# TeslaBMS_Shield_5.net
KiCad netlist of a schematic drawn in EAGLE
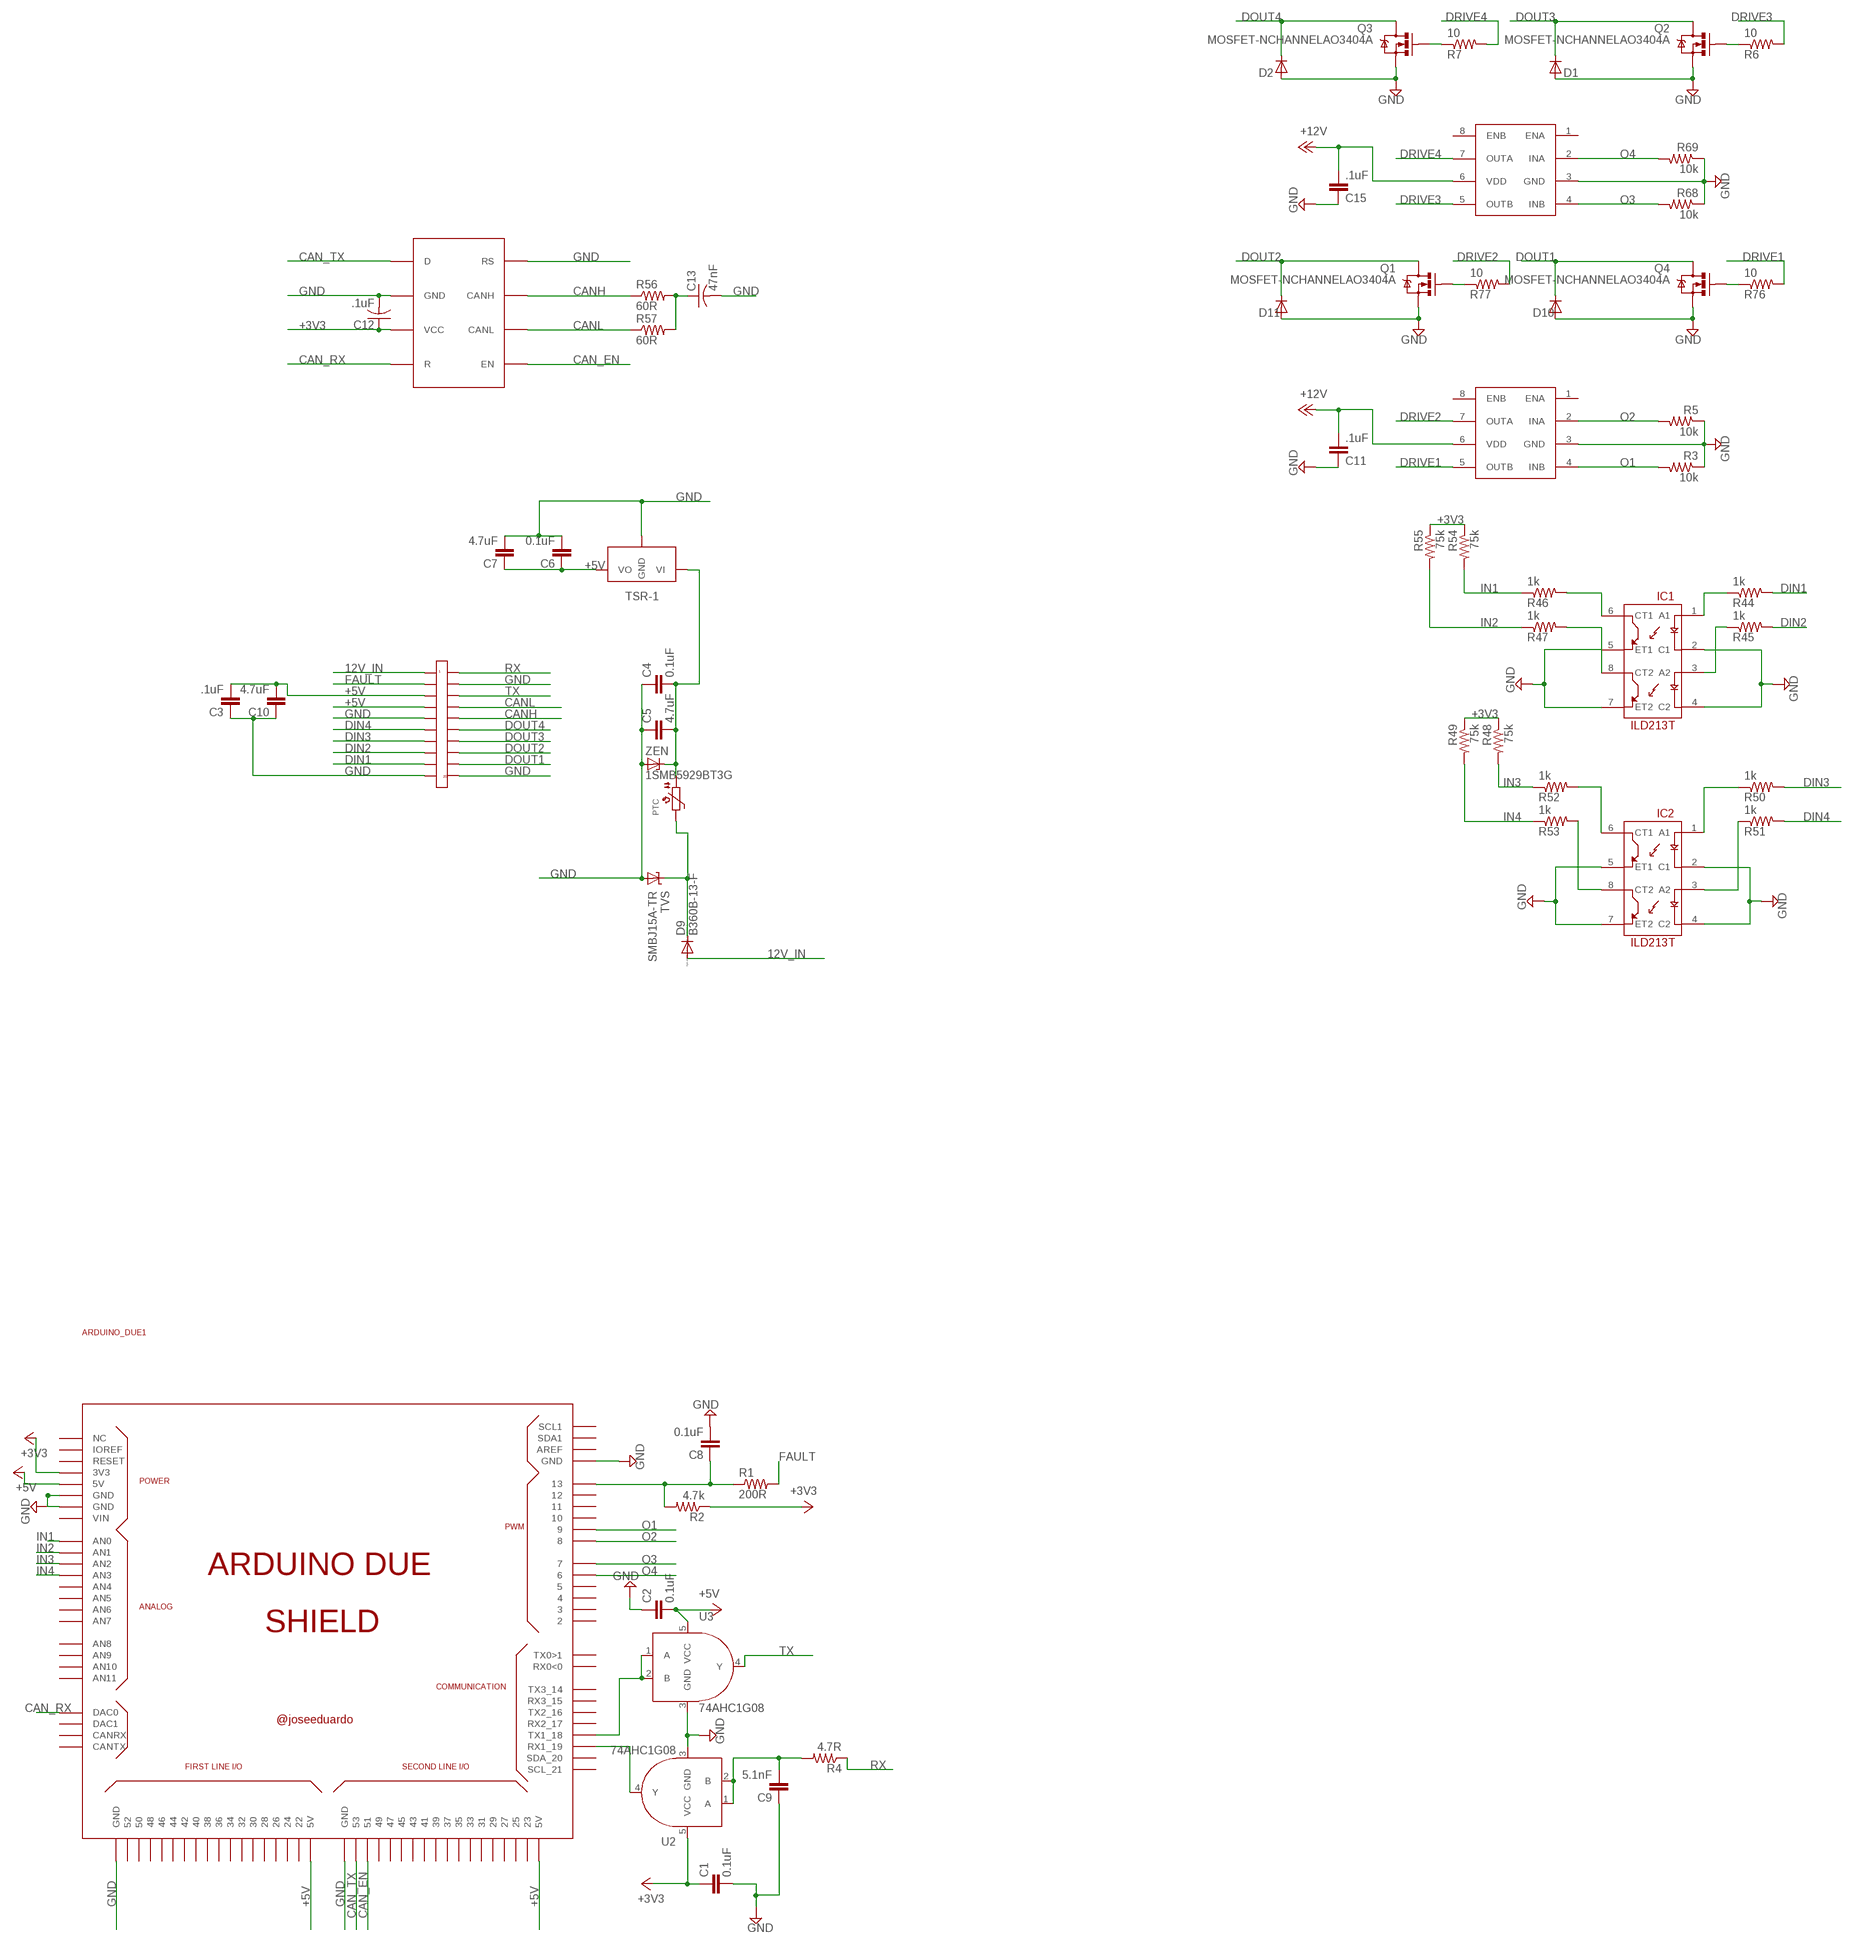
[diagram p0: schematic, sheet 1]

(export (version "E")
  (design (tool "Eeschema 10.0.6"))
  (components
    (comp (ref "ARDUINO_DUE1")
      (value "ARDUINO_DUE_SHIELD")
      (footprint "eagle-import:ARDUINO_DUE_SHIELD")
      (libsource (lib "eagle-import") (part "ARDUINO_DUE_SHIELD"))
    )
    (comp (ref "C1")
      (value "0.1uF")
      (footprint "eagle-import:0603-CAP")
      (libsource (lib "eagle-import") (part "CAP0603-CAP"))
    )
    (comp (ref "C2")
      (value "0.1uF")
      (footprint "eagle-import:0603-CAP")
      (libsource (lib "eagle-import") (part "CAP0603-CAP"))
    )
    (comp (ref "C3")
      (value ".1uF")
      (footprint "eagle-import:0603-CAP")
      (libsource (lib "eagle-import") (part "CAP0603-CAP"))
    )
    (comp (ref "C4")
      (value "0.1uF")
      (footprint "eagle-import:0805")
      (libsource (lib "eagle-import") (part "CAP0805"))
    )
    (comp (ref "C5")
      (value "4.7uF")
      (footprint "eagle-import:0805")
      (libsource (lib "eagle-import") (part "CAP0805"))
    )
    (comp (ref "C6")
      (value "0.1uF")
      (footprint "eagle-import:0805")
      (libsource (lib "eagle-import") (part "CAP0805"))
    )
    (comp (ref "C7")
      (value "4.7uF")
      (footprint "eagle-import:0805")
      (libsource (lib "eagle-import") (part "CAP0805"))
    )
    (comp (ref "C8")
      (value "0.1uF")
      (footprint "eagle-import:0603-CAP")
      (libsource (lib "eagle-import") (part "CAP0603-CAP"))
    )
    (comp (ref "C9")
      (value "5.1nF")
      (footprint "eagle-import:0603-CAP")
      (libsource (lib "eagle-import") (part "CAP0603-CAP"))
    )
    (comp (ref "C10")
      (value "4.7uF")
      (footprint "eagle-import:0603-CAP")
      (libsource (lib "eagle-import") (part "CAP0603-CAP"))
    )
    (comp (ref "C11")
      (value ".1uF")
      (footprint "eagle-import:0603-CAP")
      (libsource (lib "eagle-import") (part "CAP0603-CAP"))
    )
    (comp (ref "C12")
      (value ".1uF")
      (footprint "eagle-import:C0603")
      (libsource (lib "eagle-import") (part "C-USC0603"))
    )
    (comp (ref "C13")
      (value "47nF")
      (footprint "eagle-import:C0805")
      (libsource (lib "eagle-import") (part "C-USC0805"))
    )
    (comp (ref "C15")
      (value ".1uF")
      (footprint "eagle-import:0603-CAP")
      (libsource (lib "eagle-import") (part "CAP0603-CAP"))
    )
    (comp (ref "D1")
      (value "MBR0520LT")
      (footprint "eagle-import:SOD123")
      (libsource (lib "eagle-import") (part "MBR0520LT"))
    )
    (comp (ref "D2")
      (value "MBR0520LT")
      (footprint "eagle-import:SOD123")
      (libsource (lib "eagle-import") (part "MBR0520LT"))
    )
    (comp (ref "D9")
      (value "B360B-13-F")
      (footprint "eagle-import:SMB")
      (libsource (lib "eagle-import") (part "DIODE-SMB"))
    )
    (comp (ref "D10")
      (value "MBR0520LT")
      (footprint "eagle-import:SOD123")
      (libsource (lib "eagle-import") (part "MBR0520LT"))
    )
    (comp (ref "D11")
      (value "MBR0520LT")
      (footprint "eagle-import:SOD123")
      (libsource (lib "eagle-import") (part "MBR0520LT"))
    )
    (comp (ref "IC1")
      (value "ILD213T")
      (footprint "eagle-import:SO08")
      (libsource (lib "eagle-import") (part "ILD213T"))
    )
    (comp (ref "IC2")
      (value "ILD213T")
      (footprint "eagle-import:SO08")
      (libsource (lib "eagle-import") (part "ILD213T"))
    )
    (comp (ref "PTC")
      (value "PTC1812")
      (footprint "eagle-import:PTC1812")
      (libsource (lib "eagle-import") (part "PTC1812"))
    )
    (comp (ref "Q1")
      (value "MOSFET-NCHANNELAO3404A")
      (footprint "eagle-import:SOT23-3")
      (libsource (lib "eagle-import") (part "MOSFET-NCHANNELAO3404A"))
    )
    (comp (ref "Q2")
      (value "MOSFET-NCHANNELAO3404A")
      (footprint "eagle-import:SOT23-3")
      (libsource (lib "eagle-import") (part "MOSFET-NCHANNELAO3404A"))
    )
    (comp (ref "Q3")
      (value "MOSFET-NCHANNELAO3404A")
      (footprint "eagle-import:SOT23-3")
      (libsource (lib "eagle-import") (part "MOSFET-NCHANNELAO3404A"))
    )
    (comp (ref "Q4")
      (value "MOSFET-NCHANNELAO3404A")
      (footprint "eagle-import:SOT23-3")
      (libsource (lib "eagle-import") (part "MOSFET-NCHANNELAO3404A"))
    )
    (comp (ref "R1")
      (value "200R")
      (footprint "eagle-import:0603-RES")
      (libsource (lib "eagle-import") (part "RESISTOR0603-RES"))
    )
    (comp (ref "R2")
      (value "4.7k")
      (footprint "eagle-import:0603-RES")
      (libsource (lib "eagle-import") (part "RESISTOR0603-RES"))
    )
    (comp (ref "R3")
      (value "10k")
      (footprint "eagle-import:R0402")
      (libsource (lib "eagle-import") (part "R-US_R0402"))
    )
    (comp (ref "R4")
      (value "4.7R")
      (footprint "eagle-import:0603-RES")
      (libsource (lib "eagle-import") (part "RESISTOR0603-RES"))
    )
    (comp (ref "R5")
      (value "10k")
      (footprint "eagle-import:R0402")
      (libsource (lib "eagle-import") (part "R-US_R0402"))
    )
    (comp (ref "R6")
      (value "10")
      (footprint "eagle-import:R0402")
      (libsource (lib "eagle-import") (part "R-US_R0402"))
    )
    (comp (ref "R7")
      (value "10")
      (footprint "eagle-import:R0402")
      (libsource (lib "eagle-import") (part "R-US_R0402"))
    )
    (comp (ref "R44")
      (value "1k")
      (footprint "eagle-import:0603-RES")
      (libsource (lib "eagle-import") (part "RESISTOR0603-RES"))
    )
    (comp (ref "R45")
      (value "1k")
      (footprint "eagle-import:0603-RES")
      (libsource (lib "eagle-import") (part "RESISTOR0603-RES"))
    )
    (comp (ref "R46")
      (value "1k")
      (footprint "eagle-import:0603-RES")
      (libsource (lib "eagle-import") (part "RESISTOR0603-RES"))
    )
    (comp (ref "R47")
      (value "1k")
      (footprint "eagle-import:0603-RES")
      (libsource (lib "eagle-import") (part "RESISTOR0603-RES"))
    )
    (comp (ref "R48")
      (value "75k")
      (footprint "eagle-import:0603-RES")
      (libsource (lib "eagle-import") (part "RESISTOR0603-RES"))
    )
    (comp (ref "R49")
      (value "75k")
      (footprint "eagle-import:0603-RES")
      (libsource (lib "eagle-import") (part "RESISTOR0603-RES"))
    )
    (comp (ref "R50")
      (value "1k")
      (footprint "eagle-import:0603-RES")
      (libsource (lib "eagle-import") (part "RESISTOR0603-RES"))
    )
    (comp (ref "R51")
      (value "1k")
      (footprint "eagle-import:0603-RES")
      (libsource (lib "eagle-import") (part "RESISTOR0603-RES"))
    )
    (comp (ref "R52")
      (value "1k")
      (footprint "eagle-import:0603-RES")
      (libsource (lib "eagle-import") (part "RESISTOR0603-RES"))
    )
    (comp (ref "R53")
      (value "1k")
      (footprint "eagle-import:0603-RES")
      (libsource (lib "eagle-import") (part "RESISTOR0603-RES"))
    )
    (comp (ref "R54")
      (value "75k")
      (footprint "eagle-import:0603-RES")
      (libsource (lib "eagle-import") (part "RESISTOR0603-RES"))
    )
    (comp (ref "R55")
      (value "75k")
      (footprint "eagle-import:0603-RES")
      (libsource (lib "eagle-import") (part "RESISTOR0603-RES"))
    )
    (comp (ref "R56")
      (value "60R")
      (footprint "eagle-import:M0805")
      (libsource (lib "eagle-import") (part "R-US_M0805"))
    )
    (comp (ref "R57")
      (value "60R")
      (footprint "eagle-import:M0805")
      (libsource (lib "eagle-import") (part "R-US_M0805"))
    )
    (comp (ref "R68")
      (value "10k")
      (footprint "eagle-import:R0402")
      (libsource (lib "eagle-import") (part "R-US_R0402"))
    )
    (comp (ref "R69")
      (value "10k")
      (footprint "eagle-import:R0402")
      (libsource (lib "eagle-import") (part "R-US_R0402"))
    )
    (comp (ref "R76")
      (value "10")
      (footprint "eagle-import:R0402")
      (libsource (lib "eagle-import") (part "R-US_R0402"))
    )
    (comp (ref "R77")
      (value "10")
      (footprint "eagle-import:R0402")
      (libsource (lib "eagle-import") (part "R-US_R0402"))
    )
    (comp (ref "TVS")
      (value "SMBJ15A-TR")
      (footprint "eagle-import:SMBJ")
      (libsource (lib "eagle-import") (part "SUPPRESSOR-SMBJ"))
    )
    (comp (ref "U$2")
      (value "VAL-U-LOK-20PIN")
      (footprint "eagle-import:VALULOK-20")
      (libsource (lib "eagle-import") (part "VAL-U-LOK-20PIN"))
    )
    (comp (ref "U1")
      (value "SN65HVD234")
      (footprint "eagle-import:SOIC8")
      (libsource (lib "eagle-import") (part "SN65HVD234"))
    )
    (comp (ref "U2")
      (value "74AHC1G08")
      (footprint "eagle-import:SOT353")
      (libsource (lib "eagle-import") (part "74AHC1G08"))
    )
    (comp (ref "U3")
      (value "74AHC1G08")
      (footprint "eagle-import:SOT353")
      (libsource (lib "eagle-import") (part "74AHC1G08"))
    )
    (comp (ref "U4")
      (value "FAN3227")
      (footprint "eagle-import:SOIC8")
      (libsource (lib "eagle-import") (part "FAN3227"))
    )
    (comp (ref "U5")
      (value "FAN3227")
      (footprint "eagle-import:SOIC8")
      (libsource (lib "eagle-import") (part "FAN3227"))
    )
    (comp (ref "U9")
      (value "TSR-1")
      (footprint "eagle-import:TSR-1")
      (libsource (lib "eagle-import") (part "TSR-1"))
    )
    (comp (ref "ZEN")
      (value "1SMB5929BT3G")
      (footprint "eagle-import:SMB")
      (libsource (lib "eagle-import") (part "ZENER-DIODESMB"))
    )
  )
  (nets
    (net (code "1") (name "+3V3") (class "Default")
      (node (ref "ARDUINO_DUE1") (pin "3V3") (pinfunction "3V3_3V3") (pintype "bidirectional"))
      (node (ref "C1") (pin "1") (pinfunction "1_1") (pintype "passive"))
      (node (ref "C12") (pin "1") (pinfunction "1_1") (pintype "passive"))
      (node (ref "R2") (pin "1") (pinfunction "1_1") (pintype "passive"))
      (node (ref "R48") (pin "1") (pinfunction "1_1") (pintype "passive"))
      (node (ref "R49") (pin "1") (pinfunction "1_1") (pintype "passive"))
      (node (ref "R54") (pin "1") (pinfunction "1_1") (pintype "passive"))
      (node (ref "R55") (pin "1") (pinfunction "1_1") (pintype "passive"))
      (node (ref "U1") (pin "PIN3") (pinfunction "VCC_PIN3") (pintype "bidirectional"))
      (node (ref "U2") (pin "5") (pinfunction "VCC_5") (pintype "bidirectional"))
    )
    (net (code "2") (name "+5V") (class "Default")
      (node (ref "ARDUINO_DUE1") (pin "5V0") (pinfunction "5V_5V0") (pintype "bidirectional"))
      (node (ref "ARDUINO_DUE1") (pin "5V0_1") (pinfunction "5V_5V0_1") (pintype "bidirectional"))
      (node (ref "ARDUINO_DUE1") (pin "5V0_2") (pinfunction "5V_5V0_2") (pintype "bidirectional"))
      (node (ref "C10") (pin "2") (pinfunction "2_2") (pintype "passive"))
      (node (ref "C2") (pin "2") (pinfunction "2_2") (pintype "passive"))
      (node (ref "C3") (pin "2") (pinfunction "2_2") (pintype "passive"))
      (node (ref "C6") (pin "1") (pinfunction "1_1") (pintype "passive"))
      (node (ref "C7") (pin "1") (pinfunction "1_1") (pintype "passive"))
      (node (ref "U$2") (pin "P$3") (pinfunction "P$3_P$3") (pintype "bidirectional"))
      (node (ref "U$2") (pin "P$4") (pinfunction "P$4_P$4") (pintype "bidirectional"))
      (node (ref "U3") (pin "5") (pinfunction "VCC_5") (pintype "bidirectional"))
      (node (ref "U9") (pin "P$3") (pinfunction "VO_P$3") (pintype "bidirectional"))
    )
    (net (code "3") (name "+12V") (class "Default")
      (node (ref "C11") (pin "2") (pinfunction "2_2") (pintype "passive"))
      (node (ref "C15") (pin "2") (pinfunction "2_2") (pintype "passive"))
      (node (ref "C4") (pin "2") (pinfunction "2_2") (pintype "passive"))
      (node (ref "C5") (pin "2") (pinfunction "2_2") (pintype "passive"))
      (node (ref "PTC") (pin "P$1") (pinfunction "1_P$1") (pintype "passive"))
      (node (ref "U4") (pin "6") (pinfunction "VDD_6") (pintype "bidirectional"))
      (node (ref "U5") (pin "6") (pinfunction "VDD_6") (pintype "bidirectional"))
      (node (ref "U9") (pin "P$1") (pinfunction "VI_P$1") (pintype "bidirectional"))
      (node (ref "ZEN") (pin "C") (pinfunction "C_C") (pintype "passive"))
    )
    (net (code "4") (name "/12V_IN") (class "Default")
      (node (ref "D9") (pin "A") (pinfunction "A_A") (pintype "passive"))
      (node (ref "U$2") (pin "P$1") (pinfunction "P$1_P$1") (pintype "bidirectional"))
    )
    (net (code "5") (name "/CANH") (class "Default")
      (node (ref "R56") (pin "1") (pinfunction "1_1") (pintype "passive"))
      (node (ref "U$2") (pin "P$15") (pinfunction "P$15_P$15") (pintype "bidirectional"))
      (node (ref "U1") (pin "PIN7") (pinfunction "CANH_PIN7") (pintype "bidirectional"))
    )
    (net (code "6") (name "/CANL") (class "Default")
      (node (ref "R57") (pin "1") (pinfunction "1_1") (pintype "passive"))
      (node (ref "U$2") (pin "P$14") (pinfunction "P$14_P$14") (pintype "bidirectional"))
      (node (ref "U1") (pin "PIN6") (pinfunction "CANL_PIN6") (pintype "bidirectional"))
    )
    (net (code "7") (name "/CAN_EN") (class "Default")
      (node (ref "ARDUINO_DUE1") (pin "51") (pinfunction "51_51") (pintype "bidirectional"))
      (node (ref "U1") (pin "PIN5") (pinfunction "EN_PIN5") (pintype "bidirectional"))
    )
    (net (code "8") (name "/CAN_RX") (class "Default")
      (node (ref "ARDUINO_DUE1") (pin "DAC0") (pinfunction "DAC0_DAC0") (pintype "bidirectional"))
      (node (ref "U1") (pin "PIN4") (pinfunction "R_PIN4") (pintype "bidirectional"))
    )
    (net (code "9") (name "/CAN_TX") (class "Default")
      (node (ref "ARDUINO_DUE1") (pin "53") (pinfunction "53_53") (pintype "bidirectional"))
      (node (ref "U1") (pin "PIN1") (pinfunction "D_PIN1") (pintype "bidirectional"))
    )
    (net (code "10") (name "/DIN1") (class "Default")
      (node (ref "R44") (pin "2") (pinfunction "2_2") (pintype "passive"))
      (node (ref "U$2") (pin "P$9") (pinfunction "P$9_P$9") (pintype "bidirectional"))
    )
    (net (code "11") (name "/DIN2") (class "Default")
      (node (ref "R45") (pin "2") (pinfunction "2_2") (pintype "passive"))
      (node (ref "U$2") (pin "P$8") (pinfunction "P$8_P$8") (pintype "bidirectional"))
    )
    (net (code "12") (name "/DIN3") (class "Default")
      (node (ref "R50") (pin "2") (pinfunction "2_2") (pintype "passive"))
      (node (ref "U$2") (pin "P$7") (pinfunction "P$7_P$7") (pintype "bidirectional"))
    )
    (net (code "13") (name "/DIN4") (class "Default")
      (node (ref "R51") (pin "2") (pinfunction "2_2") (pintype "passive"))
      (node (ref "U$2") (pin "P$6") (pinfunction "P$6_P$6") (pintype "bidirectional"))
    )
    (net (code "14") (name "/DOUT1") (class "Default")
      (node (ref "D10") (pin "C") (pinfunction "C_C") (pintype "passive"))
      (node (ref "Q4") (pin "3") (pinfunction "D_3") (pintype "passive"))
      (node (ref "U$2") (pin "P$19") (pinfunction "P$19_P$19") (pintype "bidirectional"))
    )
    (net (code "15") (name "/DOUT2") (class "Default")
      (node (ref "D11") (pin "C") (pinfunction "C_C") (pintype "passive"))
      (node (ref "Q1") (pin "3") (pinfunction "D_3") (pintype "passive"))
      (node (ref "U$2") (pin "P$18") (pinfunction "P$18_P$18") (pintype "bidirectional"))
    )
    (net (code "16") (name "/DOUT3") (class "Default")
      (node (ref "D1") (pin "C") (pinfunction "C_C") (pintype "passive"))
      (node (ref "Q2") (pin "3") (pinfunction "D_3") (pintype "passive"))
      (node (ref "U$2") (pin "P$17") (pinfunction "P$17_P$17") (pintype "bidirectional"))
    )
    (net (code "17") (name "/DOUT4") (class "Default")
      (node (ref "D2") (pin "C") (pinfunction "C_C") (pintype "passive"))
      (node (ref "Q3") (pin "3") (pinfunction "D_3") (pintype "passive"))
      (node (ref "U$2") (pin "P$16") (pinfunction "P$16_P$16") (pintype "bidirectional"))
    )
    (net (code "18") (name "/DRIVE1") (class "Default")
      (node (ref "R76") (pin "2") (pinfunction "2_2") (pintype "passive"))
      (node (ref "U5") (pin "5") (pinfunction "OUTB_5") (pintype "bidirectional"))
    )
    (net (code "19") (name "/DRIVE2") (class "Default")
      (node (ref "R77") (pin "2") (pinfunction "2_2") (pintype "passive"))
      (node (ref "U5") (pin "7") (pinfunction "OUTA_7") (pintype "bidirectional"))
    )
    (net (code "20") (name "/DRIVE3") (class "Default")
      (node (ref "R6") (pin "2") (pinfunction "2_2") (pintype "passive"))
      (node (ref "U4") (pin "5") (pinfunction "OUTB_5") (pintype "bidirectional"))
    )
    (net (code "21") (name "/DRIVE4") (class "Default")
      (node (ref "R7") (pin "2") (pinfunction "2_2") (pintype "passive"))
      (node (ref "U4") (pin "7") (pinfunction "OUTA_7") (pintype "bidirectional"))
    )
    (net (code "22") (name "/FAULT") (class "Default")
      (node (ref "R1") (pin "2") (pinfunction "2_2") (pintype "passive"))
      (node (ref "U$2") (pin "P$2") (pinfunction "P$2_P$2") (pintype "bidirectional"))
    )
    (net (code "23") (name "/IN1") (class "Default")
      (node (ref "ARDUINO_DUE1") (pin "A0") (pinfunction "AN0_A0") (pintype "bidirectional"))
      (node (ref "R46") (pin "1") (pinfunction "1_1") (pintype "passive"))
      (node (ref "R54") (pin "2") (pinfunction "2_2") (pintype "passive"))
    )
    (net (code "24") (name "/IN2") (class "Default")
      (node (ref "ARDUINO_DUE1") (pin "A1") (pinfunction "AN1_A1") (pintype "bidirectional"))
      (node (ref "R47") (pin "1") (pinfunction "1_1") (pintype "passive"))
      (node (ref "R55") (pin "2") (pinfunction "2_2") (pintype "passive"))
    )
    (net (code "25") (name "/IN3") (class "Default")
      (node (ref "ARDUINO_DUE1") (pin "A2") (pinfunction "AN2_A2") (pintype "bidirectional"))
      (node (ref "R48") (pin "2") (pinfunction "2_2") (pintype "passive"))
      (node (ref "R52") (pin "1") (pinfunction "1_1") (pintype "passive"))
    )
    (net (code "26") (name "/IN4") (class "Default")
      (node (ref "ARDUINO_DUE1") (pin "A3") (pinfunction "AN3_A3") (pintype "bidirectional"))
      (node (ref "R49") (pin "2") (pinfunction "2_2") (pintype "passive"))
      (node (ref "R53") (pin "1") (pinfunction "1_1") (pintype "passive"))
    )
    (net (code "27") (name "/O1") (class "Default")
      (node (ref "ARDUINO_DUE1") (pin "9") (pinfunction "9_9") (pintype "bidirectional"))
      (node (ref "R3") (pin "2") (pinfunction "2_2") (pintype "passive"))
      (node (ref "U5") (pin "4") (pinfunction "INB_4") (pintype "bidirectional"))
    )
    (net (code "28") (name "/O2") (class "Default")
      (node (ref "ARDUINO_DUE1") (pin "8") (pinfunction "8_8") (pintype "bidirectional"))
      (node (ref "R5") (pin "2") (pinfunction "2_2") (pintype "passive"))
      (node (ref "U5") (pin "2") (pinfunction "INA_2") (pintype "bidirectional"))
    )
    (net (code "29") (name "/O3") (class "Default")
      (node (ref "ARDUINO_DUE1") (pin "7") (pinfunction "7_7") (pintype "bidirectional"))
      (node (ref "R68") (pin "2") (pinfunction "2_2") (pintype "passive"))
      (node (ref "U4") (pin "4") (pinfunction "INB_4") (pintype "bidirectional"))
    )
    (net (code "30") (name "/O4") (class "Default")
      (node (ref "ARDUINO_DUE1") (pin "6") (pinfunction "6_6") (pintype "bidirectional"))
      (node (ref "R69") (pin "2") (pinfunction "2_2") (pintype "passive"))
      (node (ref "U4") (pin "2") (pinfunction "INA_2") (pintype "bidirectional"))
    )
    (net (code "31") (name "/RX") (class "Default")
      (node (ref "R4") (pin "1") (pinfunction "1_1") (pintype "passive"))
      (node (ref "U$2") (pin "P$11") (pinfunction "P$11_P$11") (pintype "bidirectional"))
    )
    (net (code "32") (name "/TX") (class "Default")
      (node (ref "U$2") (pin "P$13") (pinfunction "P$13_P$13") (pintype "bidirectional"))
      (node (ref "U3") (pin "4") (pinfunction "Y_4") (pintype "bidirectional"))
    )
    (net (code "33") (name "GND") (class "Default")
      (node (ref "ARDUINO_DUE1") (pin "GND") (pinfunction "GND_GND") (pintype "bidirectional"))
      (node (ref "ARDUINO_DUE1") (pin "GND_1") (pinfunction "GND_GND_1") (pintype "bidirectional"))
      (node (ref "ARDUINO_DUE1") (pin "GND_2") (pinfunction "GND_GND_2") (pintype "bidirectional"))
      (node (ref "ARDUINO_DUE1") (pin "GND_3") (pinfunction "GND_GND_3") (pintype "bidirectional"))
      (node (ref "ARDUINO_DUE1") (pin "GND_4") (pinfunction "GND_GND_4") (pintype "bidirectional"))
      (node (ref "C1") (pin "2") (pinfunction "2_2") (pintype "passive"))
      (node (ref "C10") (pin "1") (pinfunction "1_1") (pintype "passive"))
      (node (ref "C11") (pin "1") (pinfunction "1_1") (pintype "passive"))
      (node (ref "C12") (pin "2") (pinfunction "2_2") (pintype "passive"))
      (node (ref "C13") (pin "2") (pinfunction "2_2") (pintype "passive"))
      (node (ref "C15") (pin "1") (pinfunction "1_1") (pintype "passive"))
      (node (ref "C2") (pin "1") (pinfunction "1_1") (pintype "passive"))
      (node (ref "C3") (pin "1") (pinfunction "1_1") (pintype "passive"))
      (node (ref "C4") (pin "1") (pinfunction "1_1") (pintype "passive"))
      (node (ref "C5") (pin "1") (pinfunction "1_1") (pintype "passive"))
      (node (ref "C6") (pin "2") (pinfunction "2_2") (pintype "passive"))
      (node (ref "C7") (pin "2") (pinfunction "2_2") (pintype "passive"))
      (node (ref "C8") (pin "2") (pinfunction "2_2") (pintype "passive"))
      (node (ref "C9") (pin "1") (pinfunction "1_1") (pintype "passive"))
      (node (ref "D1") (pin "A") (pinfunction "A_A") (pintype "passive"))
      (node (ref "D10") (pin "A") (pinfunction "A_A") (pintype "passive"))
      (node (ref "D11") (pin "A") (pinfunction "A_A") (pintype "passive"))
      (node (ref "D2") (pin "A") (pinfunction "A_A") (pintype "passive"))
      (node (ref "IC1") (pin "2") (pinfunction "C1_2") (pintype "bidirectional"))
      (node (ref "IC1") (pin "4") (pinfunction "C2_4") (pintype "bidirectional"))
      (node (ref "IC1") (pin "5") (pinfunction "ET1_5") (pintype "bidirectional"))
      (node (ref "IC1") (pin "7") (pinfunction "ET2_7") (pintype "bidirectional"))
      (node (ref "IC2") (pin "2") (pinfunction "C1_2") (pintype "bidirectional"))
      (node (ref "IC2") (pin "4") (pinfunction "C2_4") (pintype "bidirectional"))
      (node (ref "IC2") (pin "5") (pinfunction "ET1_5") (pintype "bidirectional"))
      (node (ref "IC2") (pin "7") (pinfunction "ET2_7") (pintype "bidirectional"))
      (node (ref "Q1") (pin "2") (pinfunction "S_2") (pintype "passive"))
      (node (ref "Q2") (pin "2") (pinfunction "S_2") (pintype "passive"))
      (node (ref "Q3") (pin "2") (pinfunction "S_2") (pintype "passive"))
      (node (ref "Q4") (pin "2") (pinfunction "S_2") (pintype "passive"))
      (node (ref "R3") (pin "1") (pinfunction "1_1") (pintype "passive"))
      (node (ref "R5") (pin "1") (pinfunction "1_1") (pintype "passive"))
      (node (ref "R68") (pin "1") (pinfunction "1_1") (pintype "passive"))
      (node (ref "R69") (pin "1") (pinfunction "1_1") (pintype "passive"))
      (node (ref "TVS") (pin "A") (pinfunction "A_A") (pintype "passive"))
      (node (ref "U$2") (pin "P$10") (pinfunction "P$10_P$10") (pintype "bidirectional"))
      (node (ref "U$2") (pin "P$12") (pinfunction "P$12_P$12") (pintype "bidirectional"))
      (node (ref "U$2") (pin "P$20") (pinfunction "P$20_P$20") (pintype "bidirectional"))
      (node (ref "U$2") (pin "P$5") (pinfunction "P$5_P$5") (pintype "bidirectional"))
      (node (ref "U1") (pin "PIN2") (pinfunction "GND_PIN2") (pintype "bidirectional"))
      (node (ref "U1") (pin "PIN8") (pinfunction "RS_PIN8") (pintype "bidirectional"))
      (node (ref "U2") (pin "3") (pinfunction "GND_3") (pintype "bidirectional"))
      (node (ref "U3") (pin "3") (pinfunction "GND_3") (pintype "bidirectional"))
      (node (ref "U4") (pin "3") (pinfunction "GND_3") (pintype "bidirectional"))
      (node (ref "U5") (pin "3") (pinfunction "GND_3") (pintype "bidirectional"))
      (node (ref "U9") (pin "P$2") (pinfunction "GND_P$2") (pintype "bidirectional"))
      (node (ref "ZEN") (pin "A") (pinfunction "A_A") (pintype "passive"))
    )
    (net (code "34") (name "Net-(ARDUINO_DUE1-Pad13)") (class "Default")
      (node (ref "ARDUINO_DUE1") (pin "13") (pinfunction "13_13") (pintype "bidirectional"))
      (node (ref "C8") (pin "1") (pinfunction "1_1") (pintype "passive"))
      (node (ref "R1") (pin "1") (pinfunction "1_1") (pintype "passive"))
      (node (ref "R2") (pin "2") (pinfunction "2_2") (pintype "passive"))
    )
    (net (code "35") (name "Net-(ARDUINO_DUE1-RX1_19)") (class "Default")
      (node (ref "ARDUINO_DUE1") (pin "19") (pinfunction "RX1_19_19") (pintype "bidirectional"))
      (node (ref "U2") (pin "4") (pinfunction "Y_4") (pintype "bidirectional"))
    )
    (net (code "36") (name "Net-(ARDUINO_DUE1-TX1_18)") (class "Default")
      (node (ref "ARDUINO_DUE1") (pin "18") (pinfunction "TX1_18_18") (pintype "bidirectional"))
      (node (ref "U3") (pin "1") (pinfunction "A_1") (pintype "bidirectional"))
      (node (ref "U3") (pin "2") (pinfunction "B_2") (pintype "bidirectional"))
    )
    (net (code "37") (name "Net-(C13-Pad1)") (class "Default")
      (node (ref "C13") (pin "1") (pinfunction "1_1") (pintype "passive"))
      (node (ref "R56") (pin "2") (pinfunction "2_2") (pintype "passive"))
      (node (ref "R57") (pin "2") (pinfunction "2_2") (pintype "passive"))
    )
    (net (code "38") (name "Net-(IC1-A1)") (class "Default")
      (node (ref "IC1") (pin "1") (pinfunction "A1_1") (pintype "bidirectional"))
      (node (ref "R44") (pin "1") (pinfunction "1_1") (pintype "passive"))
    )
    (net (code "39") (name "Net-(IC1-A2)") (class "Default")
      (node (ref "IC1") (pin "3") (pinfunction "A2_3") (pintype "bidirectional"))
      (node (ref "R45") (pin "1") (pinfunction "1_1") (pintype "passive"))
    )
    (net (code "40") (name "Net-(IC1-CT1)") (class "Default")
      (node (ref "IC1") (pin "6") (pinfunction "CT1_6") (pintype "bidirectional"))
      (node (ref "R46") (pin "2") (pinfunction "2_2") (pintype "passive"))
    )
    (net (code "41") (name "Net-(IC1-CT2)") (class "Default")
      (node (ref "IC1") (pin "8") (pinfunction "CT2_8") (pintype "bidirectional"))
      (node (ref "R47") (pin "2") (pinfunction "2_2") (pintype "passive"))
    )
    (net (code "42") (name "Net-(IC2-A1)") (class "Default")
      (node (ref "IC2") (pin "1") (pinfunction "A1_1") (pintype "bidirectional"))
      (node (ref "R50") (pin "1") (pinfunction "1_1") (pintype "passive"))
    )
    (net (code "43") (name "Net-(IC2-A2)") (class "Default")
      (node (ref "IC2") (pin "3") (pinfunction "A2_3") (pintype "bidirectional"))
      (node (ref "R51") (pin "1") (pinfunction "1_1") (pintype "passive"))
    )
    (net (code "44") (name "Net-(IC2-CT1)") (class "Default")
      (node (ref "IC2") (pin "6") (pinfunction "CT1_6") (pintype "bidirectional"))
      (node (ref "R52") (pin "2") (pinfunction "2_2") (pintype "passive"))
    )
    (net (code "45") (name "Net-(IC2-CT2)") (class "Default")
      (node (ref "IC2") (pin "8") (pinfunction "CT2_8") (pintype "bidirectional"))
      (node (ref "R53") (pin "2") (pinfunction "2_2") (pintype "passive"))
    )
    (net (code "46") (name "Net-(PTC-2)") (class "Default")
      (node (ref "D9") (pin "C") (pinfunction "C_C") (pintype "passive"))
      (node (ref "PTC") (pin "P$2") (pinfunction "2_P$2") (pintype "passive"))
      (node (ref "TVS") (pin "C") (pinfunction "C_C") (pintype "passive"))
    )
    (net (code "47") (name "Net-(Q1-G)") (class "Default")
      (node (ref "Q1") (pin "1") (pinfunction "G_1") (pintype "passive"))
      (node (ref "R77") (pin "1") (pinfunction "1_1") (pintype "passive"))
    )
    (net (code "48") (name "Net-(Q2-G)") (class "Default")
      (node (ref "Q2") (pin "1") (pinfunction "G_1") (pintype "passive"))
      (node (ref "R6") (pin "1") (pinfunction "1_1") (pintype "passive"))
    )
    (net (code "49") (name "Net-(Q3-G)") (class "Default")
      (node (ref "Q3") (pin "1") (pinfunction "G_1") (pintype "passive"))
      (node (ref "R7") (pin "1") (pinfunction "1_1") (pintype "passive"))
    )
    (net (code "50") (name "Net-(Q4-G)") (class "Default")
      (node (ref "Q4") (pin "1") (pinfunction "G_1") (pintype "passive"))
      (node (ref "R76") (pin "1") (pinfunction "1_1") (pintype "passive"))
    )
    (net (code "51") (name "Net-(U2-A)") (class "Default")
      (node (ref "C9") (pin "2") (pinfunction "2_2") (pintype "passive"))
      (node (ref "R4") (pin "2") (pinfunction "2_2") (pintype "passive"))
      (node (ref "U2") (pin "1") (pinfunction "A_1") (pintype "bidirectional"))
      (node (ref "U2") (pin "2") (pinfunction "B_2") (pintype "bidirectional"))
    )
    (net (code "52") (name "unconnected-(ARDUINO_DUE1-AN4-PadA4)") (class "Default")
      (node (ref "ARDUINO_DUE1") (pin "A4") (pinfunction "AN4_A4") (pintype "bidirectional"))
    )
    (net (code "53") (name "unconnected-(ARDUINO_DUE1-AN5-PadA5)") (class "Default")
      (node (ref "ARDUINO_DUE1") (pin "A5") (pinfunction "AN5_A5") (pintype "bidirectional"))
    )
    (net (code "54") (name "unconnected-(ARDUINO_DUE1-AN6-PadA6)") (class "Default")
      (node (ref "ARDUINO_DUE1") (pin "A6") (pinfunction "AN6_A6") (pintype "bidirectional"))
    )
    (net (code "55") (name "unconnected-(ARDUINO_DUE1-AN7-PadA7)") (class "Default")
      (node (ref "ARDUINO_DUE1") (pin "A7") (pinfunction "AN7_A7") (pintype "bidirectional"))
    )
    (net (code "56") (name "unconnected-(ARDUINO_DUE1-AN8-PadA8)") (class "Default")
      (node (ref "ARDUINO_DUE1") (pin "A8") (pinfunction "AN8_A8") (pintype "bidirectional"))
    )
    (net (code "57") (name "unconnected-(ARDUINO_DUE1-AN9-PadA9)") (class "Default")
      (node (ref "ARDUINO_DUE1") (pin "A9") (pinfunction "AN9_A9") (pintype "bidirectional"))
    )
    (net (code "58") (name "unconnected-(ARDUINO_DUE1-AN10-PadA10)") (class "Default")
      (node (ref "ARDUINO_DUE1") (pin "A10") (pinfunction "AN10_A10") (pintype "bidirectional"))
    )
    (net (code "59") (name "unconnected-(ARDUINO_DUE1-AN11-PadA11)") (class "Default")
      (node (ref "ARDUINO_DUE1") (pin "A11") (pinfunction "AN11_A11") (pintype "bidirectional"))
    )
    (net (code "60") (name "unconnected-(ARDUINO_DUE1-NC-PadNC_2)") (class "Default")
      (node (ref "ARDUINO_DUE1") (pin "NC_2") (pinfunction "NC_NC_2") (pintype "no_connect"))
    )
    (net (code "61") (name "unconnected-(ARDUINO_DUE1-Pad2)") (class "Default")
      (node (ref "ARDUINO_DUE1") (pin "2") (pinfunction "2_2") (pintype "bidirectional"))
    )
    (net (code "62") (name "unconnected-(ARDUINO_DUE1-Pad3)") (class "Default")
      (node (ref "ARDUINO_DUE1") (pin "3") (pinfunction "3_3") (pintype "bidirectional"))
    )
    (net (code "63") (name "unconnected-(ARDUINO_DUE1-Pad4)") (class "Default")
      (node (ref "ARDUINO_DUE1") (pin "4") (pinfunction "4_4") (pintype "bidirectional"))
    )
    (net (code "64") (name "unconnected-(ARDUINO_DUE1-Pad5)") (class "Default")
      (node (ref "ARDUINO_DUE1") (pin "5") (pinfunction "5_5") (pintype "bidirectional"))
    )
    (net (code "65") (name "unconnected-(ARDUINO_DUE1-Pad10)") (class "Default")
      (node (ref "ARDUINO_DUE1") (pin "10") (pinfunction "10_10") (pintype "bidirectional"))
    )
    (net (code "66") (name "unconnected-(ARDUINO_DUE1-Pad11)") (class "Default")
      (node (ref "ARDUINO_DUE1") (pin "11") (pinfunction "11_11") (pintype "bidirectional"))
    )
    (net (code "67") (name "unconnected-(ARDUINO_DUE1-Pad12)") (class "Default")
      (node (ref "ARDUINO_DUE1") (pin "12") (pinfunction "12_12") (pintype "bidirectional"))
    )
    (net (code "68") (name "unconnected-(ARDUINO_DUE1-Pad22)") (class "Default")
      (node (ref "ARDUINO_DUE1") (pin "22") (pinfunction "22_22") (pintype "bidirectional"))
    )
    (net (code "69") (name "unconnected-(ARDUINO_DUE1-Pad23)") (class "Default")
      (node (ref "ARDUINO_DUE1") (pin "23") (pinfunction "23_23") (pintype "bidirectional"))
    )
    (net (code "70") (name "unconnected-(ARDUINO_DUE1-Pad24)") (class "Default")
      (node (ref "ARDUINO_DUE1") (pin "24") (pinfunction "24_24") (pintype "bidirectional"))
    )
    (net (code "71") (name "unconnected-(ARDUINO_DUE1-Pad25)") (class "Default")
      (node (ref "ARDUINO_DUE1") (pin "25") (pinfunction "25_25") (pintype "bidirectional"))
    )
    (net (code "72") (name "unconnected-(ARDUINO_DUE1-Pad26)") (class "Default")
      (node (ref "ARDUINO_DUE1") (pin "26") (pinfunction "26_26") (pintype "bidirectional"))
    )
    (net (code "73") (name "unconnected-(ARDUINO_DUE1-Pad27)") (class "Default")
      (node (ref "ARDUINO_DUE1") (pin "27") (pinfunction "27_27") (pintype "bidirectional"))
    )
    (net (code "74") (name "unconnected-(ARDUINO_DUE1-Pad28)") (class "Default")
      (node (ref "ARDUINO_DUE1") (pin "28") (pinfunction "28_28") (pintype "bidirectional"))
    )
    (net (code "75") (name "unconnected-(ARDUINO_DUE1-Pad29)") (class "Default")
      (node (ref "ARDUINO_DUE1") (pin "29") (pinfunction "29_29") (pintype "bidirectional"))
    )
    (net (code "76") (name "unconnected-(ARDUINO_DUE1-Pad30)") (class "Default")
      (node (ref "ARDUINO_DUE1") (pin "30") (pinfunction "30_30") (pintype "bidirectional"))
    )
    (net (code "77") (name "unconnected-(ARDUINO_DUE1-Pad31)") (class "Default")
      (node (ref "ARDUINO_DUE1") (pin "31") (pinfunction "31_31") (pintype "bidirectional"))
    )
    (net (code "78") (name "unconnected-(ARDUINO_DUE1-Pad32)") (class "Default")
      (node (ref "ARDUINO_DUE1") (pin "32") (pinfunction "32_32") (pintype "bidirectional"))
    )
    (net (code "79") (name "unconnected-(ARDUINO_DUE1-Pad33)") (class "Default")
      (node (ref "ARDUINO_DUE1") (pin "33") (pinfunction "33_33") (pintype "bidirectional"))
    )
    (net (code "80") (name "unconnected-(ARDUINO_DUE1-Pad34)") (class "Default")
      (node (ref "ARDUINO_DUE1") (pin "34") (pinfunction "34_34") (pintype "bidirectional"))
    )
    (net (code "81") (name "unconnected-(ARDUINO_DUE1-Pad35)") (class "Default")
      (node (ref "ARDUINO_DUE1") (pin "35") (pinfunction "35_35") (pintype "bidirectional"))
    )
    (net (code "82") (name "unconnected-(ARDUINO_DUE1-Pad36)") (class "Default")
      (node (ref "ARDUINO_DUE1") (pin "36") (pinfunction "36_36") (pintype "bidirectional"))
    )
    (net (code "83") (name "unconnected-(ARDUINO_DUE1-Pad37)") (class "Default")
      (node (ref "ARDUINO_DUE1") (pin "37") (pinfunction "37_37") (pintype "bidirectional"))
    )
    (net (code "84") (name "unconnected-(ARDUINO_DUE1-Pad38)") (class "Default")
      (node (ref "ARDUINO_DUE1") (pin "38") (pinfunction "38_38") (pintype "bidirectional"))
    )
    (net (code "85") (name "unconnected-(ARDUINO_DUE1-Pad39)") (class "Default")
      (node (ref "ARDUINO_DUE1") (pin "39") (pinfunction "39_39") (pintype "bidirectional"))
    )
    (net (code "86") (name "unconnected-(ARDUINO_DUE1-Pad40)") (class "Default")
      (node (ref "ARDUINO_DUE1") (pin "40") (pinfunction "40_40") (pintype "bidirectional"))
    )
    (net (code "87") (name "unconnected-(ARDUINO_DUE1-Pad41)") (class "Default")
      (node (ref "ARDUINO_DUE1") (pin "41") (pinfunction "41_41") (pintype "bidirectional"))
    )
    (net (code "88") (name "unconnected-(ARDUINO_DUE1-Pad42)") (class "Default")
      (node (ref "ARDUINO_DUE1") (pin "42") (pinfunction "42_42") (pintype "bidirectional"))
    )
    (net (code "89") (name "unconnected-(ARDUINO_DUE1-Pad43)") (class "Default")
      (node (ref "ARDUINO_DUE1") (pin "43") (pinfunction "43_43") (pintype "bidirectional"))
    )
    (net (code "90") (name "unconnected-(ARDUINO_DUE1-Pad44)") (class "Default")
      (node (ref "ARDUINO_DUE1") (pin "44") (pinfunction "44_44") (pintype "bidirectional"))
    )
    (net (code "91") (name "unconnected-(ARDUINO_DUE1-Pad45)") (class "Default")
      (node (ref "ARDUINO_DUE1") (pin "45") (pinfunction "45_45") (pintype "bidirectional"))
    )
    (net (code "92") (name "unconnected-(ARDUINO_DUE1-Pad46)") (class "Default")
      (node (ref "ARDUINO_DUE1") (pin "46") (pinfunction "46_46") (pintype "bidirectional"))
    )
    (net (code "93") (name "unconnected-(ARDUINO_DUE1-Pad47)") (class "Default")
      (node (ref "ARDUINO_DUE1") (pin "47") (pinfunction "47_47") (pintype "bidirectional"))
    )
    (net (code "94") (name "unconnected-(ARDUINO_DUE1-Pad48)") (class "Default")
      (node (ref "ARDUINO_DUE1") (pin "48") (pinfunction "48_48") (pintype "bidirectional"))
    )
    (net (code "95") (name "unconnected-(ARDUINO_DUE1-Pad49)") (class "Default")
      (node (ref "ARDUINO_DUE1") (pin "49") (pinfunction "49_49") (pintype "bidirectional"))
    )
    (net (code "96") (name "unconnected-(ARDUINO_DUE1-Pad50)") (class "Default")
      (node (ref "ARDUINO_DUE1") (pin "50") (pinfunction "50_50") (pintype "bidirectional"))
    )
    (net (code "97") (name "unconnected-(ARDUINO_DUE1-Pad52)") (class "Default")
      (node (ref "ARDUINO_DUE1") (pin "52") (pinfunction "52_52") (pintype "bidirectional"))
    )
    (net (code "98") (name "unconnected-(ARDUINO_DUE1-PadAREF)") (class "Default")
      (node (ref "ARDUINO_DUE1") (pin "AREF") (pinfunction "AREF_AREF") (pintype "bidirectional"))
    )
    (net (code "99") (name "unconnected-(ARDUINO_DUE1-PadCANRX)") (class "Default")
      (node (ref "ARDUINO_DUE1") (pin "CANRX") (pinfunction "CANRX_CANRX") (pintype "bidirectional"))
    )
    (net (code "100") (name "unconnected-(ARDUINO_DUE1-PadCANTX)") (class "Default")
      (node (ref "ARDUINO_DUE1") (pin "CANTX") (pinfunction "CANTX_CANTX") (pintype "bidirectional"))
    )
    (net (code "101") (name "unconnected-(ARDUINO_DUE1-PadDAC1)") (class "Default")
      (node (ref "ARDUINO_DUE1") (pin "DAC1") (pinfunction "DAC1_DAC1") (pintype "bidirectional"))
    )
    (net (code "102") (name "unconnected-(ARDUINO_DUE1-PadIOREF)") (class "Default")
      (node (ref "ARDUINO_DUE1") (pin "IOREF") (pinfunction "IOREF_IOREF") (pintype "bidirectional"))
    )
    (net (code "103") (name "unconnected-(ARDUINO_DUE1-PadRESET)") (class "Default")
      (node (ref "ARDUINO_DUE1") (pin "RESET") (pinfunction "RESET_RESET") (pintype "bidirectional"))
    )
    (net (code "104") (name "unconnected-(ARDUINO_DUE1-PadSCL1)") (class "Default")
      (node (ref "ARDUINO_DUE1") (pin "SCL1") (pinfunction "SCL1_SCL1") (pintype "bidirectional"))
    )
    (net (code "105") (name "unconnected-(ARDUINO_DUE1-PadSDA1)") (class "Default")
      (node (ref "ARDUINO_DUE1") (pin "SDA1") (pinfunction "SDA1_SDA1") (pintype "bidirectional"))
    )
    (net (code "106") (name "unconnected-(ARDUINO_DUE1-PadVIN)") (class "Default")
      (node (ref "ARDUINO_DUE1") (pin "VIN") (pinfunction "VIN_VIN") (pintype "bidirectional"))
    )
    (net (code "107") (name "unconnected-(ARDUINO_DUE1-RX0<0-Pad0)") (class "Default")
      (node (ref "ARDUINO_DUE1") (pin "0") (pinfunction "RX0<0_0") (pintype "bidirectional"))
    )
    (net (code "108") (name "unconnected-(ARDUINO_DUE1-RX2_17-Pad17)") (class "Default")
      (node (ref "ARDUINO_DUE1") (pin "17") (pinfunction "RX2_17_17") (pintype "bidirectional"))
    )
    (net (code "109") (name "unconnected-(ARDUINO_DUE1-RX3_15-Pad15)") (class "Default")
      (node (ref "ARDUINO_DUE1") (pin "15") (pinfunction "RX3_15_15") (pintype "bidirectional"))
    )
    (net (code "110") (name "unconnected-(ARDUINO_DUE1-SCL_21-Pad21)") (class "Default")
      (node (ref "ARDUINO_DUE1") (pin "21") (pinfunction "SCL_21_21") (pintype "bidirectional"))
    )
    (net (code "111") (name "unconnected-(ARDUINO_DUE1-SDA_20-Pad20)") (class "Default")
      (node (ref "ARDUINO_DUE1") (pin "20") (pinfunction "SDA_20_20") (pintype "bidirectional"))
    )
    (net (code "112") (name "unconnected-(ARDUINO_DUE1-TX0>1-Pad1)") (class "Default")
      (node (ref "ARDUINO_DUE1") (pin "1") (pinfunction "TX0>1_1") (pintype "bidirectional"))
    )
    (net (code "113") (name "unconnected-(ARDUINO_DUE1-TX2_16-Pad16)") (class "Default")
      (node (ref "ARDUINO_DUE1") (pin "16") (pinfunction "TX2_16_16") (pintype "bidirectional"))
    )
    (net (code "114") (name "unconnected-(ARDUINO_DUE1-TX3_14-Pad14)") (class "Default")
      (node (ref "ARDUINO_DUE1") (pin "14") (pinfunction "TX3_14_14") (pintype "bidirectional"))
    )
    (net (code "115") (name "unconnected-(U4-ENA-Pad1)") (class "Default")
      (node (ref "U4") (pin "1") (pinfunction "ENA_1") (pintype "bidirectional"))
    )
    (net (code "116") (name "unconnected-(U4-ENB-Pad8)") (class "Default")
      (node (ref "U4") (pin "8") (pinfunction "ENB_8") (pintype "bidirectional"))
    )
    (net (code "117") (name "unconnected-(U5-ENA-Pad1)") (class "Default")
      (node (ref "U5") (pin "1") (pinfunction "ENA_1") (pintype "bidirectional"))
    )
    (net (code "118") (name "unconnected-(U5-ENB-Pad8)") (class "Default")
      (node (ref "U5") (pin "8") (pinfunction "ENB_8") (pintype "bidirectional"))
    )
  )
)
